# Comm_board_2024_M8N.net
KiCad netlist of a schematic drawn in EAGLE
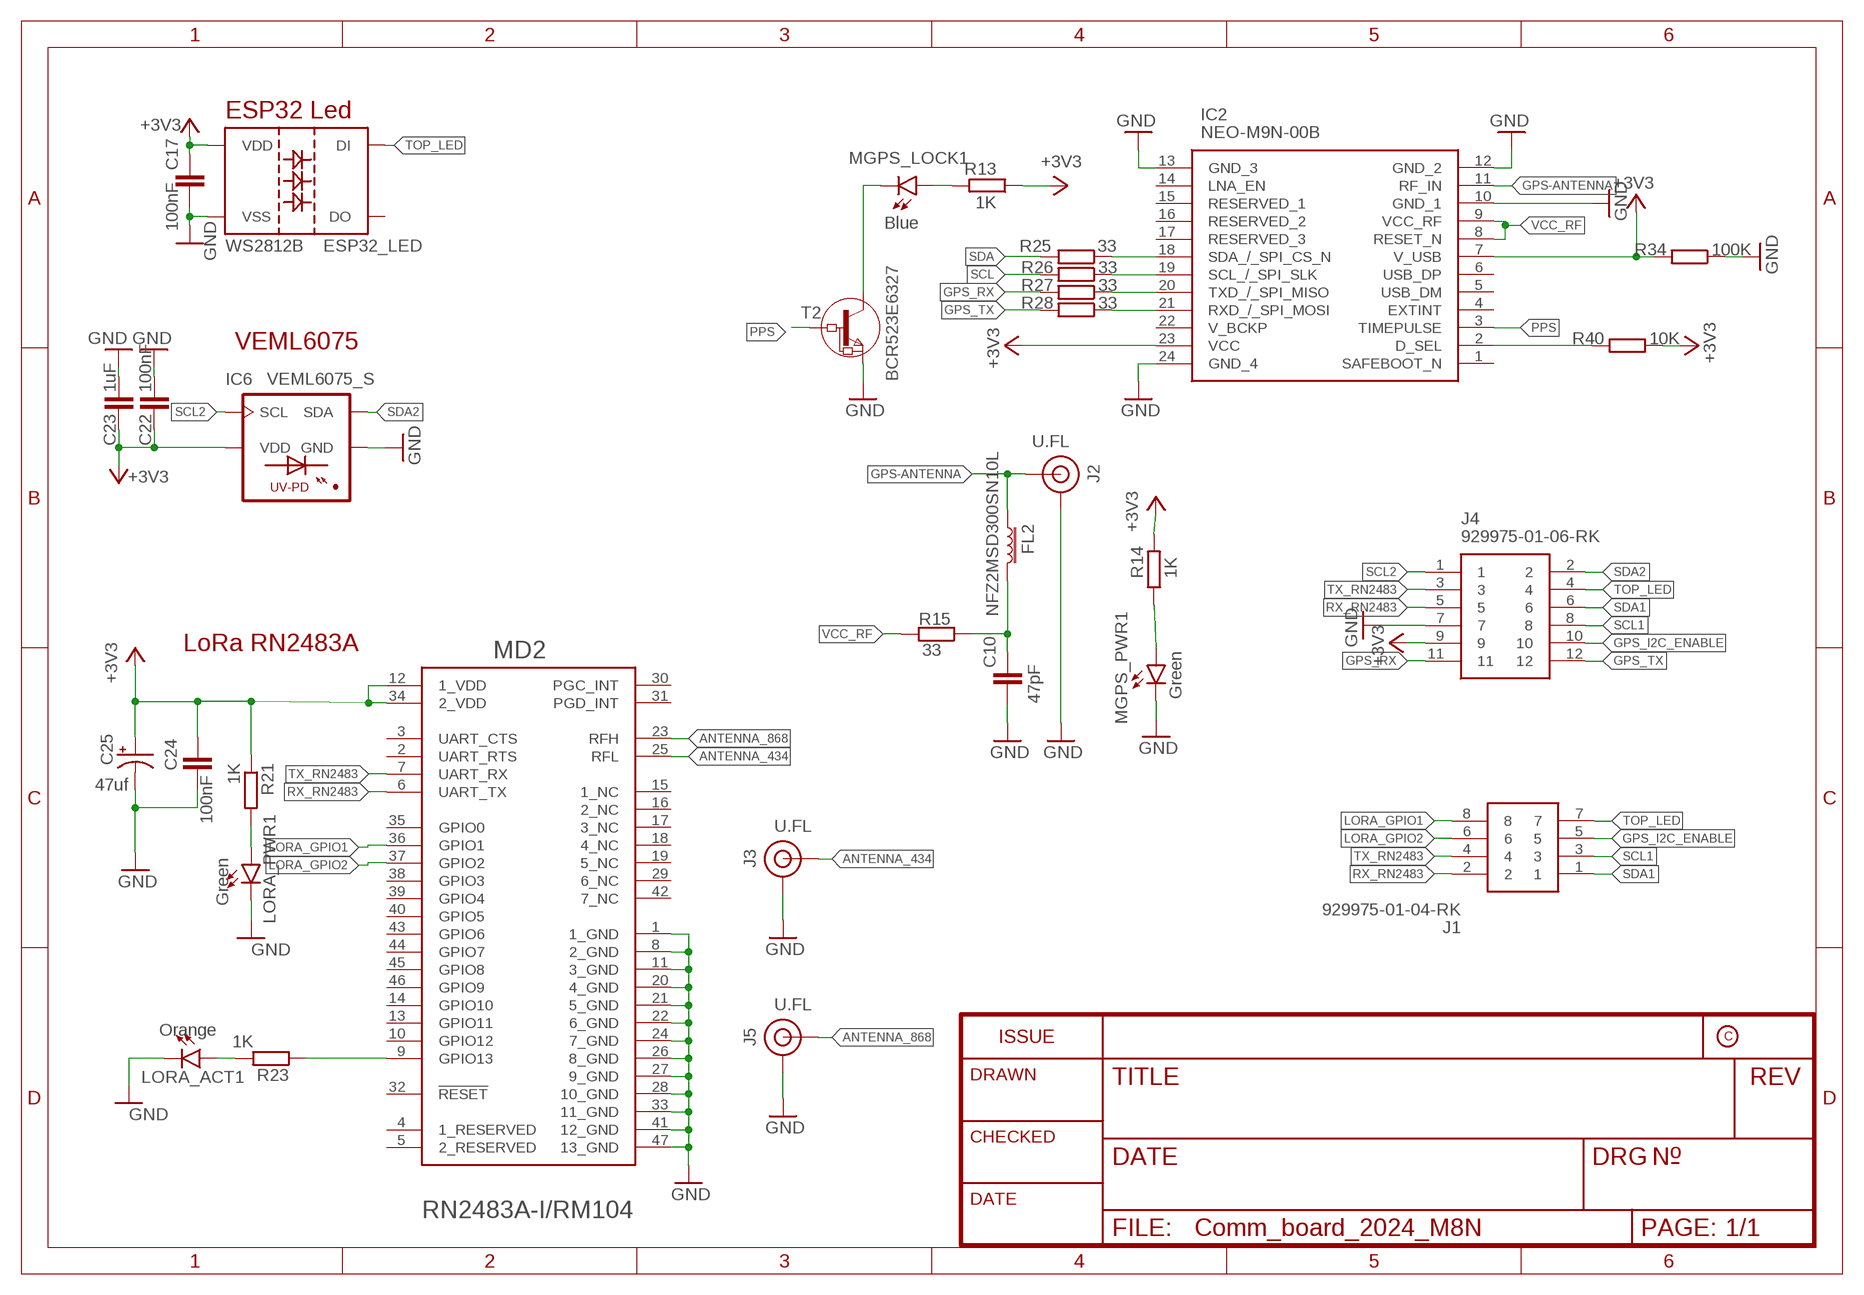
[diagram p0: schematic, sheet 1]

(export (version "E")
  (design (tool "Eeschema 10.0.6"))
  (components
    (comp (ref "C10")
      (value "47pF")
      (footprint "eagle-import:C0603")
      (libsource (lib "eagle-import") (part "C-EUC0603"))
    )
    (comp (ref "C17")
      (value "100nF")
      (footprint "eagle-import:C0603")
      (libsource (lib "eagle-import") (part "C-EUC0603"))
    )
    (comp (ref "C22")
      (value "100nF")
      (footprint "eagle-import:C0603")
      (libsource (lib "eagle-import") (part "C-EUC0603"))
    )
    (comp (ref "C23")
      (value "1uF")
      (footprint "eagle-import:C0603")
      (libsource (lib "eagle-import") (part "C-EUC0603"))
    )
    (comp (ref "C24")
      (value "100nF")
      (footprint "eagle-import:C0603")
      (libsource (lib "eagle-import") (part "C-EUC0603"))
    )
    (comp (ref "C25")
      (value "47uf")
      (footprint "eagle-import:CAPMP6032X250N")
      (fields (field (name "MF") "Vishay") (field (name "MP") "293D226X9025C2TE3"))
      (libsource (lib "eagle-import") (part "293D226X9025C2TE3"))
    )
    (comp (ref "ESP32_LED")
      (value "WS2812B")
      (footprint "eagle-import:WS2812B")
      (libsource (lib "eagle-import") (part "WS2812B"))
    )
    (comp (ref "FL2")
      (value "NFZ2MSD300SN10L")
      (footprint "eagle-import:BEADC2016X120N")
      (fields (field (name "MF") "Murata"))
      (libsource (lib "eagle-import") (part "NFZ2MSD300SN10L"))
    )
    (comp (ref "IC2")
      (value "NEO-M9N-00B")
      (footprint "eagle-import:NEOM9N00B")
      (fields (field (name "MOUSER_PART_NUMBER") "377-NEO-M9N-00B"))
      (libsource (lib "eagle-import") (part "NEO-M9N-00B"))
    )
    (comp (ref "IC6")
      (value "VEML6075_S")
      (footprint "eagle-import:VISHAY_VEML6075_1.25X2X1")
      (fields
        (field (name "DIGI-KEY_PART_NUMBER") "VEML6075CT-ND")
        (field (name "MF") "Vishay Semiconductor")
        (field (name "MP") "VEML6075")
      )
      (libsource (lib "eagle-import") (part "VEML6075_S"))
    )
    (comp (ref "J1")
      (value "929975-01-04-RK")
      (footprint "eagle-import:RHDR8W76P254_2X4_1016X508X839P")
      (fields (field (name "MOUSER_PART_NUMBER") "517-929975-01-04-RK"))
      (libsource (lib "eagle-import") (part "929975-01-04-RK"))
    )
    (comp (ref "J2")
      (value "U.FL")
      (footprint "eagle-import:SPARKFUN-CONNECTORS_SPARKFUN-CONNECTORS_U.FL")
      (libsource (lib "eagle-import") (part "SPARKFUN-CONNECTORS_SPARKFUN-CONNECTORS_U.FL2PIN"))
    )
    (comp (ref "J3")
      (value "U.FL")
      (footprint "eagle-import:SPARKFUN-CONNECTORS_SPARKFUN-CONNECTORS_U.FL")
      (libsource (lib "eagle-import") (part "SPARKFUN-CONNECTORS_SPARKFUN-CONNECTORS_U.FL2PIN"))
    )
    (comp (ref "J4")
      (value "929975-01-06-RK")
      (footprint "eagle-import:RHDR12W76P254_2X6_1524X508X839")
      (fields (field (name "MOUSER_PART_NUMBER") "517-929975-01-06-RK"))
      (libsource (lib "eagle-import") (part "929975-01-06-RK"))
    )
    (comp (ref "J5")
      (value "U.FL")
      (footprint "eagle-import:SPARKFUN-CONNECTORS_SPARKFUN-CONNECTORS_U.FL")
      (libsource (lib "eagle-import") (part "SPARKFUN-CONNECTORS_SPARKFUN-CONNECTORS_U.FL2PIN"))
    )
    (comp (ref "LORA_ACT1")
      (value "Orange")
      (footprint "eagle-import:CHIP-LED0603")
      (libsource (lib "eagle-import") (part "LEDCHIP-LED0603"))
    )
    (comp (ref "LORA_PWR1")
      (value "Green")
      (footprint "eagle-import:CHIP-LED0603")
      (libsource (lib "eagle-import") (part "LEDCHIP-LED0603"))
    )
    (comp (ref "MD2")
      (value "RM104_MICROCHIP_RN2483A-I-RM104MICROCHIP_RN2483A-I-RM104_0_0")
      (footprint "eagle-import:RM104_MICROCHIP_RN2483A-I-RM104_0")
      (fields
        (field (name "DIGIKEY_PART_NUMBER") "RN2483A-I/RM104-ND")
        (field (name "MF") "Microchip")
        (field (name "MOUSER_PART_NUMBER") "579-RN2483A-I/RM104")
      )
      (libsource (lib "eagle-import") (part "RM104_MICROCHIP_RN2483A-I-RM104MICROCHIP_RN2483A-I-RM104_0_0"))
    )
    (comp (ref "MGPS_LOCK1")
      (value "Blue")
      (footprint "eagle-import:CHIP-LED0603")
      (libsource (lib "eagle-import") (part "LEDCHIP-LED0603"))
    )
    (comp (ref "MGPS_PWR1")
      (value "Green")
      (footprint "eagle-import:CHIP-LED0603")
      (libsource (lib "eagle-import") (part "LEDCHIP-LED0603"))
    )
    (comp (ref "R13")
      (value "1K")
      (footprint "eagle-import:R0603")
      (libsource (lib "eagle-import") (part "R-EU_R0603"))
    )
    (comp (ref "R14")
      (value "1K")
      (footprint "eagle-import:R0603")
      (libsource (lib "eagle-import") (part "R-EU_R0603"))
    )
    (comp (ref "R15")
      (value "33")
      (footprint "eagle-import:R0603")
      (libsource (lib "eagle-import") (part "R-EU_R0603"))
    )
    (comp (ref "R21")
      (value "1K")
      (footprint "eagle-import:R0603")
      (libsource (lib "eagle-import") (part "R-EU_R0603"))
    )
    (comp (ref "R23")
      (value "1K")
      (footprint "eagle-import:R0603")
      (libsource (lib "eagle-import") (part "R-EU_R0603"))
    )
    (comp (ref "R25")
      (value "33")
      (footprint "eagle-import:R0603")
      (libsource (lib "eagle-import") (part "R-EU_R0603"))
    )
    (comp (ref "R26")
      (value "33")
      (footprint "eagle-import:R0603")
      (libsource (lib "eagle-import") (part "R-EU_R0603"))
    )
    (comp (ref "R27")
      (value "33")
      (footprint "eagle-import:R0603")
      (libsource (lib "eagle-import") (part "R-EU_R0603"))
    )
    (comp (ref "R28")
      (value "33")
      (footprint "eagle-import:R0603")
      (libsource (lib "eagle-import") (part "R-EU_R0603"))
    )
    (comp (ref "R34")
      (value "100K")
      (footprint "eagle-import:R0603")
      (libsource (lib "eagle-import") (part "R-EU_R0603"))
    )
    (comp (ref "R40")
      (value "10K")
      (footprint "eagle-import:R0603")
      (libsource (lib "eagle-import") (part "R-EU_R0603"))
    )
    (comp (ref "T2")
      (value "BCR523E6327")
      (footprint "eagle-import:SOT-23")
      (fields (field (name "MPN") "DSS20201L-7"))
      (libsource (lib "eagle-import") (part "NPNSOT23"))
    )
  )
  (nets
    (net (code "1") (name "+3V3") (class "Default")
      (node (ref "C17") (pin "1") (pinfunction "1_1") (pintype "passive"))
      (node (ref "C22") (pin "2") (pinfunction "2_2") (pintype "passive"))
      (node (ref "C23") (pin "1") (pinfunction "1_1") (pintype "passive"))
      (node (ref "C24") (pin "1") (pinfunction "1_1") (pintype "passive"))
      (node (ref "C25") (pin "1") (pinfunction "+_1") (pintype "passive"))
      (node (ref "ESP32_LED") (pin "1") (pinfunction "VDD_1") (pintype "bidirectional"))
      (node (ref "IC2") (pin "23") (pinfunction "VCC_23") (pintype "bidirectional"))
      (node (ref "IC2") (pin "7") (pinfunction "V_USB_7") (pintype "bidirectional"))
      (node (ref "IC6") (pin "4") (pinfunction "VDD_4") (pintype "power_in"))
      (node (ref "J4") (pin "9") (pinfunction "9_9") (pintype "bidirectional"))
      (node (ref "MD2") (pin "12") (pinfunction "1_VDD_12") (pintype "bidirectional"))
      (node (ref "MD2") (pin "34") (pinfunction "2_VDD_34") (pintype "bidirectional"))
      (node (ref "R13") (pin "1") (pinfunction "1_1") (pintype "passive"))
      (node (ref "R14") (pin "2") (pinfunction "2_2") (pintype "passive"))
      (node (ref "R21") (pin "1") (pinfunction "1_1") (pintype "passive"))
      (node (ref "R34") (pin "2") (pinfunction "2_2") (pintype "passive"))
      (node (ref "R40") (pin "1") (pinfunction "1_1") (pintype "passive"))
    )
    (net (code "2") (name "ANTENNA_434") (class "Default")
      (node (ref "J3") (pin "FEED") (pinfunction "SIGNAL_FEED") (pintype "bidirectional"))
      (node (ref "MD2") (pin "25") (pinfunction "RFL_25") (pintype "bidirectional"))
    )
    (net (code "3") (name "ANTENNA_868") (class "Default")
      (node (ref "J5") (pin "FEED") (pinfunction "SIGNAL_FEED") (pintype "bidirectional"))
      (node (ref "MD2") (pin "23") (pinfunction "RFH_23") (pintype "bidirectional"))
    )
    (net (code "4") (name "GND") (class "Default")
      (node (ref "C10") (pin "2") (pinfunction "2_2") (pintype "passive"))
      (node (ref "C17") (pin "2") (pinfunction "2_2") (pintype "passive"))
      (node (ref "C22") (pin "1") (pinfunction "1_1") (pintype "passive"))
      (node (ref "C23") (pin "2") (pinfunction "2_2") (pintype "passive"))
      (node (ref "C24") (pin "2") (pinfunction "2_2") (pintype "passive"))
      (node (ref "C25") (pin "2") (pinfunction "-_2") (pintype "passive"))
      (node (ref "ESP32_LED") (pin "3") (pinfunction "VSS_3") (pintype "bidirectional"))
      (node (ref "IC2") (pin "10") (pinfunction "GND_1_10") (pintype "bidirectional"))
      (node (ref "IC2") (pin "12") (pinfunction "GND_2_12") (pintype "bidirectional"))
      (node (ref "IC2") (pin "13") (pinfunction "GND_3_13") (pintype "bidirectional"))
      (node (ref "IC2") (pin "24") (pinfunction "GND_4_24") (pintype "bidirectional"))
      (node (ref "IC6") (pin "1") (pinfunction "GND_1") (pintype "power_in"))
      (node (ref "J2") (pin "1") (pinfunction "GND_1") (pintype "bidirectional"))
      (node (ref "J2") (pin "2") (pinfunction "GND_2") (pintype "bidirectional"))
      (node (ref "J2") (pin "3") (pinfunction "GND_3") (pintype "bidirectional"))
      (node (ref "J3") (pin "1") (pinfunction "GND_1") (pintype "bidirectional"))
      (node (ref "J3") (pin "2") (pinfunction "GND_2") (pintype "bidirectional"))
      (node (ref "J3") (pin "3") (pinfunction "GND_3") (pintype "bidirectional"))
      (node (ref "J4") (pin "7") (pinfunction "7_7") (pintype "bidirectional"))
      (node (ref "J5") (pin "1") (pinfunction "GND_1") (pintype "bidirectional"))
      (node (ref "J5") (pin "2") (pinfunction "GND_2") (pintype "bidirectional"))
      (node (ref "J5") (pin "3") (pinfunction "GND_3") (pintype "bidirectional"))
      (node (ref "LORA_ACT1") (pin "C") (pinfunction "C_C") (pintype "passive"))
      (node (ref "LORA_PWR1") (pin "C") (pinfunction "C_C") (pintype "passive"))
      (node (ref "MD2") (pin "1") (pinfunction "1_GND_1") (pintype "bidirectional"))
      (node (ref "MD2") (pin "11") (pinfunction "3_GND_11") (pintype "bidirectional"))
      (node (ref "MD2") (pin "20") (pinfunction "4_GND_20") (pintype "bidirectional"))
      (node (ref "MD2") (pin "21") (pinfunction "5_GND_21") (pintype "bidirectional"))
      (node (ref "MD2") (pin "22") (pinfunction "6_GND_22") (pintype "bidirectional"))
      (node (ref "MD2") (pin "24") (pinfunction "7_GND_24") (pintype "bidirectional"))
      (node (ref "MD2") (pin "26") (pinfunction "8_GND_26") (pintype "bidirectional"))
      (node (ref "MD2") (pin "27") (pinfunction "9_GND_27") (pintype "bidirectional"))
      (node (ref "MD2") (pin "28") (pinfunction "10_GND_28") (pintype "bidirectional"))
      (node (ref "MD2") (pin "33") (pinfunction "11_GND_33") (pintype "bidirectional"))
      (node (ref "MD2") (pin "41") (pinfunction "12_GND_41") (pintype "bidirectional"))
      (node (ref "MD2") (pin "47") (pinfunction "13_GND_47") (pintype "bidirectional"))
      (node (ref "MD2") (pin "8") (pinfunction "2_GND_8") (pintype "bidirectional"))
      (node (ref "MGPS_PWR1") (pin "C") (pinfunction "C_C") (pintype "passive"))
      (node (ref "R34") (pin "1") (pinfunction "1_1") (pintype "passive"))
      (node (ref "T2") (pin "2") (pinfunction "E_2") (pintype "passive"))
    )
    (net (code "5") (name "GPS-ANTENNA") (class "Default")
      (node (ref "FL2") (pin "1") (pinfunction "3_1") (pintype "passive"))
      (node (ref "IC2") (pin "11") (pinfunction "RF_IN_11") (pintype "bidirectional"))
      (node (ref "J2") (pin "FEED") (pinfunction "SIGNAL_FEED") (pintype "bidirectional"))
    )
    (net (code "6") (name "GPS_I2C_ENABLE") (class "Default")
      (node (ref "J1") (pin "5") (pinfunction "5_5") (pintype "bidirectional"))
      (node (ref "J4") (pin "10") (pinfunction "10_10") (pintype "bidirectional"))
    )
    (net (code "7") (name "GPS_RX") (class "Default")
      (node (ref "J4") (pin "11") (pinfunction "11_11") (pintype "bidirectional"))
      (node (ref "R27") (pin "2") (pinfunction "2_2") (pintype "passive"))
    )
    (net (code "8") (name "GPS_TX") (class "Default")
      (node (ref "J4") (pin "12") (pinfunction "12_12") (pintype "bidirectional"))
      (node (ref "R28") (pin "2") (pinfunction "2_2") (pintype "passive"))
    )
    (net (code "9") (name "LORA_GPIO1") (class "Default")
      (node (ref "J1") (pin "8") (pinfunction "8_8") (pintype "bidirectional"))
      (node (ref "MD2") (pin "36") (pinfunction "GPIO1_36") (pintype "bidirectional"))
    )
    (net (code "10") (name "LORA_GPIO2") (class "Default")
      (node (ref "J1") (pin "6") (pinfunction "6_6") (pintype "bidirectional"))
      (node (ref "MD2") (pin "37") (pinfunction "GPIO2_37") (pintype "bidirectional"))
    )
    (net (code "11") (name "Net-(FL2-4)") (class "Default")
      (node (ref "C10") (pin "1") (pinfunction "1_1") (pintype "passive"))
      (node (ref "FL2") (pin "2") (pinfunction "4_2") (pintype "passive"))
      (node (ref "R15") (pin "1") (pinfunction "1_1") (pintype "passive"))
    )
    (net (code "12") (name "Net-(IC2-D_SEL)") (class "Default")
      (node (ref "IC2") (pin "2") (pinfunction "D_SEL_2") (pintype "bidirectional"))
      (node (ref "R40") (pin "2") (pinfunction "2_2") (pintype "passive"))
    )
    (net (code "13") (name "Net-(IC2-RXD_{slash}_SPI_MOSI)") (class "Default")
      (node (ref "IC2") (pin "21") (pinfunction "RXD_/_SPI_MOSI_21") (pintype "bidirectional"))
      (node (ref "R28") (pin "1") (pinfunction "1_1") (pintype "passive"))
    )
    (net (code "14") (name "Net-(IC2-SCL_{slash}_SPI_SLK)") (class "Default")
      (node (ref "IC2") (pin "19") (pinfunction "SCL_/_SPI_SLK_19") (pintype "bidirectional"))
      (node (ref "R26") (pin "1") (pinfunction "1_1") (pintype "passive"))
    )
    (net (code "15") (name "Net-(IC2-SDA_{slash}_SPI_CS_N)") (class "Default")
      (node (ref "IC2") (pin "18") (pinfunction "SDA_/_SPI_CS_N_18") (pintype "bidirectional"))
      (node (ref "R25") (pin "1") (pinfunction "1_1") (pintype "passive"))
    )
    (net (code "16") (name "Net-(IC2-TXD_{slash}_SPI_MISO)") (class "Default")
      (node (ref "IC2") (pin "20") (pinfunction "TXD_/_SPI_MISO_20") (pintype "bidirectional"))
      (node (ref "R27") (pin "1") (pinfunction "1_1") (pintype "passive"))
    )
    (net (code "17") (name "Net-(LORA_ACT1-PadA)") (class "Default")
      (node (ref "LORA_ACT1") (pin "A") (pinfunction "A_A") (pintype "passive"))
      (node (ref "R23") (pin "2") (pinfunction "2_2") (pintype "passive"))
    )
    (net (code "18") (name "Net-(LORA_PWR1-PadA)") (class "Default")
      (node (ref "LORA_PWR1") (pin "A") (pinfunction "A_A") (pintype "passive"))
      (node (ref "R21") (pin "2") (pinfunction "2_2") (pintype "passive"))
    )
    (net (code "19") (name "Net-(MD2-GPIO13)") (class "Default")
      (node (ref "MD2") (pin "9") (pinfunction "GPIO13_9") (pintype "bidirectional"))
      (node (ref "R23") (pin "1") (pinfunction "1_1") (pintype "passive"))
    )
    (net (code "20") (name "Net-(MGPS_LOCK1-PadA)") (class "Default")
      (node (ref "MGPS_LOCK1") (pin "A") (pinfunction "A_A") (pintype "passive"))
      (node (ref "R13") (pin "2") (pinfunction "2_2") (pintype "passive"))
    )
    (net (code "21") (name "Net-(MGPS_PWR1-PadA)") (class "Default")
      (node (ref "MGPS_PWR1") (pin "A") (pinfunction "A_A") (pintype "passive"))
      (node (ref "R14") (pin "1") (pinfunction "1_1") (pintype "passive"))
    )
    (net (code "22") (name "Net-(T2-C)") (class "Default")
      (node (ref "MGPS_LOCK1") (pin "C") (pinfunction "C_C") (pintype "passive"))
      (node (ref "T2") (pin "1") (pinfunction "C_1") (pintype "passive"))
    )
    (net (code "23") (name "PPS") (class "Default")
      (node (ref "IC2") (pin "3") (pinfunction "TIMEPULSE_3") (pintype "bidirectional"))
      (node (ref "T2") (pin "3") (pinfunction "B_3") (pintype "passive"))
    )
    (net (code "24") (name "RX_RN2483") (class "Default")
      (node (ref "J1") (pin "2") (pinfunction "2_2") (pintype "bidirectional"))
      (node (ref "J4") (pin "5") (pinfunction "5_5") (pintype "bidirectional"))
      (node (ref "MD2") (pin "6") (pinfunction "UART_TX_6") (pintype "bidirectional"))
    )
    (net (code "25") (name "SCL") (class "Default")
      (node (ref "R26") (pin "2") (pinfunction "2_2") (pintype "passive"))
    )
    (net (code "26") (name "SCL1") (class "Default")
      (node (ref "J1") (pin "3") (pinfunction "3_3") (pintype "bidirectional"))
      (node (ref "J4") (pin "8") (pinfunction "8_8") (pintype "bidirectional"))
    )
    (net (code "27") (name "SCL2") (class "Default")
      (node (ref "IC6") (pin "3") (pinfunction "SCL_3") (pintype "input"))
      (node (ref "J4") (pin "1") (pinfunction "1_1") (pintype "bidirectional"))
    )
    (net (code "28") (name "SDA") (class "Default")
      (node (ref "R25") (pin "2") (pinfunction "2_2") (pintype "passive"))
    )
    (net (code "29") (name "SDA1") (class "Default")
      (node (ref "J1") (pin "1") (pinfunction "1_1") (pintype "bidirectional"))
      (node (ref "J4") (pin "6") (pinfunction "6_6") (pintype "bidirectional"))
    )
    (net (code "30") (name "SDA2") (class "Default")
      (node (ref "IC6") (pin "2") (pinfunction "SDA_2") (pintype "bidirectional"))
      (node (ref "J4") (pin "2") (pinfunction "2_2") (pintype "bidirectional"))
    )
    (net (code "31") (name "TOP_LED") (class "Default")
      (node (ref "ESP32_LED") (pin "4") (pinfunction "DI_4") (pintype "bidirectional"))
      (node (ref "J1") (pin "7") (pinfunction "7_7") (pintype "bidirectional"))
      (node (ref "J4") (pin "4") (pinfunction "4_4") (pintype "bidirectional"))
    )
    (net (code "32") (name "TX_RN2483") (class "Default")
      (node (ref "J1") (pin "4") (pinfunction "4_4") (pintype "bidirectional"))
      (node (ref "J4") (pin "3") (pinfunction "3_3") (pintype "bidirectional"))
      (node (ref "MD2") (pin "7") (pinfunction "UART_RX_7") (pintype "bidirectional"))
    )
    (net (code "33") (name "VCC_RF") (class "Default")
      (node (ref "IC2") (pin "8") (pinfunction "RESET_N_8") (pintype "bidirectional"))
      (node (ref "IC2") (pin "9") (pinfunction "VCC_RF_9") (pintype "bidirectional"))
      (node (ref "R15") (pin "2") (pinfunction "2_2") (pintype "passive"))
    )
    (net (code "34") (name "unconnected-(ESP32_LED-DO-Pad2)") (class "Default")
      (node (ref "ESP32_LED") (pin "2") (pinfunction "DO_2") (pintype "bidirectional"))
    )
    (net (code "35") (name "unconnected-(IC2-EXTINT-Pad4)") (class "Default")
      (node (ref "IC2") (pin "4") (pinfunction "EXTINT_4") (pintype "bidirectional"))
    )
    (net (code "36") (name "unconnected-(IC2-LNA_EN-Pad14)") (class "Default")
      (node (ref "IC2") (pin "14") (pinfunction "LNA_EN_14") (pintype "bidirectional"))
    )
    (net (code "37") (name "unconnected-(IC2-RESERVED_1-Pad15)") (class "Default")
      (node (ref "IC2") (pin "15") (pinfunction "RESERVED_1_15") (pintype "bidirectional"))
    )
    (net (code "38") (name "unconnected-(IC2-RESERVED_2-Pad16)") (class "Default")
      (node (ref "IC2") (pin "16") (pinfunction "RESERVED_2_16") (pintype "bidirectional"))
    )
    (net (code "39") (name "unconnected-(IC2-RESERVED_3-Pad17)") (class "Default")
      (node (ref "IC2") (pin "17") (pinfunction "RESERVED_3_17") (pintype "bidirectional"))
    )
    (net (code "40") (name "unconnected-(IC2-SAFEBOOT_N-Pad1)") (class "Default")
      (node (ref "IC2") (pin "1") (pinfunction "SAFEBOOT_N_1") (pintype "bidirectional"))
    )
    (net (code "41") (name "unconnected-(IC2-USB_DM-Pad5)") (class "Default")
      (node (ref "IC2") (pin "5") (pinfunction "USB_DM_5") (pintype "bidirectional"))
    )
    (net (code "42") (name "unconnected-(IC2-USB_DP-Pad6)") (class "Default")
      (node (ref "IC2") (pin "6") (pinfunction "USB_DP_6") (pintype "bidirectional"))
    )
    (net (code "43") (name "unconnected-(IC2-V_BCKP-Pad22)") (class "Default")
      (node (ref "IC2") (pin "22") (pinfunction "V_BCKP_22") (pintype "bidirectional"))
    )
    (net (code "44") (name "unconnected-(MD2-1_NC-Pad15)") (class "Default")
      (node (ref "MD2") (pin "15") (pinfunction "1_NC_15") (pintype "passive"))
    )
    (net (code "45") (name "unconnected-(MD2-1_RESERVED-Pad4)") (class "Default")
      (node (ref "MD2") (pin "4") (pinfunction "1_RESERVED_4") (pintype "passive"))
    )
    (net (code "46") (name "unconnected-(MD2-2_NC-Pad16)") (class "Default")
      (node (ref "MD2") (pin "16") (pinfunction "2_NC_16") (pintype "passive"))
    )
    (net (code "47") (name "unconnected-(MD2-2_RESERVED-Pad5)") (class "Default")
      (node (ref "MD2") (pin "5") (pinfunction "2_RESERVED_5") (pintype "passive"))
    )
    (net (code "48") (name "unconnected-(MD2-3_NC-Pad17)") (class "Default")
      (node (ref "MD2") (pin "17") (pinfunction "3_NC_17") (pintype "passive"))
    )
    (net (code "49") (name "unconnected-(MD2-4_NC-Pad18)") (class "Default")
      (node (ref "MD2") (pin "18") (pinfunction "4_NC_18") (pintype "passive"))
    )
    (net (code "50") (name "unconnected-(MD2-5_NC-Pad19)") (class "Default")
      (node (ref "MD2") (pin "19") (pinfunction "5_NC_19") (pintype "passive"))
    )
    (net (code "51") (name "unconnected-(MD2-6_NC-Pad29)") (class "Default")
      (node (ref "MD2") (pin "29") (pinfunction "6_NC_29") (pintype "passive"))
    )
    (net (code "52") (name "unconnected-(MD2-7_NC-Pad42)") (class "Default")
      (node (ref "MD2") (pin "42") (pinfunction "7_NC_42") (pintype "passive"))
    )
    (net (code "53") (name "unconnected-(MD2-GPIO0-Pad35)") (class "Default")
      (node (ref "MD2") (pin "35") (pinfunction "GPIO0_35") (pintype "bidirectional"))
    )
    (net (code "54") (name "unconnected-(MD2-GPIO3-Pad38)") (class "Default")
      (node (ref "MD2") (pin "38") (pinfunction "GPIO3_38") (pintype "bidirectional"))
    )
    (net (code "55") (name "unconnected-(MD2-GPIO4-Pad39)") (class "Default")
      (node (ref "MD2") (pin "39") (pinfunction "GPIO4_39") (pintype "bidirectional"))
    )
    (net (code "56") (name "unconnected-(MD2-GPIO5-Pad40)") (class "Default")
      (node (ref "MD2") (pin "40") (pinfunction "GPIO5_40") (pintype "bidirectional"))
    )
    (net (code "57") (name "unconnected-(MD2-GPIO6-Pad43)") (class "Default")
      (node (ref "MD2") (pin "43") (pinfunction "GPIO6_43") (pintype "bidirectional"))
    )
    (net (code "58") (name "unconnected-(MD2-GPIO7-Pad44)") (class "Default")
      (node (ref "MD2") (pin "44") (pinfunction "GPIO7_44") (pintype "bidirectional"))
    )
    (net (code "59") (name "unconnected-(MD2-GPIO8-Pad45)") (class "Default")
      (node (ref "MD2") (pin "45") (pinfunction "GPIO8_45") (pintype "bidirectional"))
    )
    (net (code "60") (name "unconnected-(MD2-GPIO9-Pad46)") (class "Default")
      (node (ref "MD2") (pin "46") (pinfunction "GPIO9_46") (pintype "bidirectional"))
    )
    (net (code "61") (name "unconnected-(MD2-GPIO10-Pad14)") (class "Default")
      (node (ref "MD2") (pin "14") (pinfunction "GPIO10_14") (pintype "bidirectional"))
    )
    (net (code "62") (name "unconnected-(MD2-GPIO11-Pad13)") (class "Default")
      (node (ref "MD2") (pin "13") (pinfunction "GPIO11_13") (pintype "bidirectional"))
    )
    (net (code "63") (name "unconnected-(MD2-GPIO12-Pad10)") (class "Default")
      (node (ref "MD2") (pin "10") (pinfunction "GPIO12_10") (pintype "bidirectional"))
    )
    (net (code "64") (name "unconnected-(MD2-PGC_INT-Pad30)") (class "Default")
      (node (ref "MD2") (pin "30") (pinfunction "PGC_INT_30") (pintype "bidirectional"))
    )
    (net (code "65") (name "unconnected-(MD2-PGD_INT-Pad31)") (class "Default")
      (node (ref "MD2") (pin "31") (pinfunction "PGD_INT_31") (pintype "bidirectional"))
    )
    (net (code "66") (name "unconnected-(MD2-UART_CTS-Pad3)") (class "Default")
      (node (ref "MD2") (pin "3") (pinfunction "UART_CTS_3") (pintype "bidirectional"))
    )
    (net (code "67") (name "unconnected-(MD2-UART_RTS-Pad2)") (class "Default")
      (node (ref "MD2") (pin "2") (pinfunction "UART_RTS_2") (pintype "bidirectional"))
    )
    (net (code "68") (name "unconnected-(MD2-~{RESET}-Pad32)") (class "Default")
      (node (ref "MD2") (pin "32") (pinfunction "~{RESET}_32") (pintype "bidirectional"))
    )
  )
)
